# garden_control2.net
KiCad netlist of a schematic drawn in EAGLE
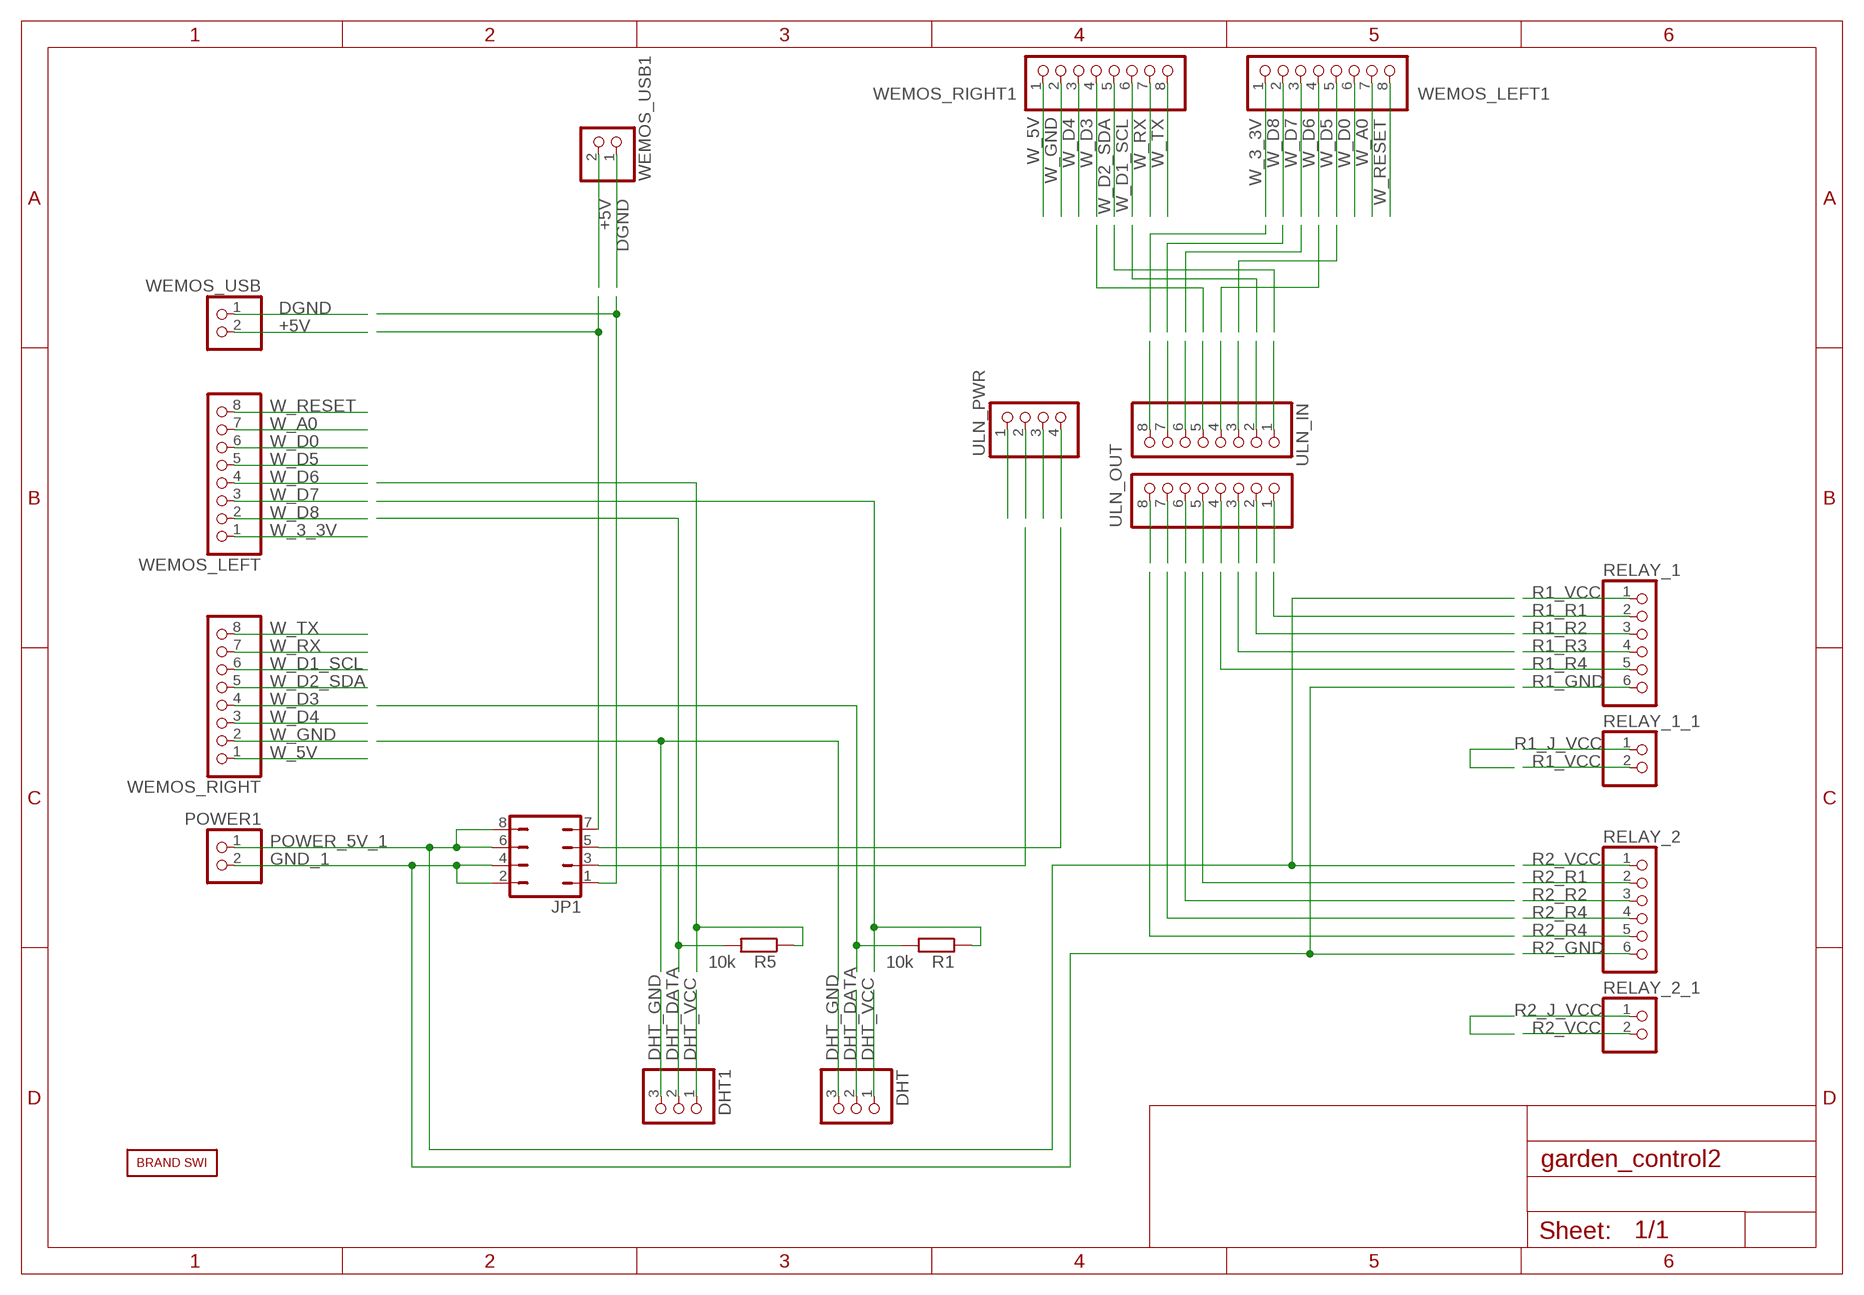
[diagram p0: schematic, sheet 1]

(export (version "E")
  (design (tool "Eeschema 10.0.6"))
  (components
    (comp (ref "DHT")
      (value "PINHD-1X3")
      (footprint "eagle-import:1X03")
      (libsource (lib "eagle-import") (part "PINHD-1X3"))
    )
    (comp (ref "DHT1")
      (value "PINHD-1X3")
      (footprint "eagle-import:1X03")
      (libsource (lib "eagle-import") (part "PINHD-1X3"))
    )
    (comp (ref "JP1")
      (value "JP4Q")
      (footprint "eagle-import:JP4Q")
      (libsource (lib "eagle-import") (part "JP4Q"))
    )
    (comp (ref "POWER1")
      (value "PINHD-1X2")
      (footprint "eagle-import:1X02")
      (libsource (lib "eagle-import") (part "PINHD-1X2"))
    )
    (comp (ref "R1")
      (value "10k")
      (footprint "eagle-import:0207_10")
      (libsource (lib "eagle-import") (part "R-EU_0207/10"))
    )
    (comp (ref "R5")
      (value "10k")
      (footprint "eagle-import:0207_10")
      (libsource (lib "eagle-import") (part "R-EU_0207/10"))
    )
    (comp (ref "RELAY_1")
      (value "PINHD-1X6")
      (footprint "eagle-import:1X06")
      (libsource (lib "eagle-import") (part "PINHD-1X6"))
    )
    (comp (ref "RELAY_1_1")
      (value "PINHD-1X2")
      (footprint "eagle-import:1X02")
      (libsource (lib "eagle-import") (part "PINHD-1X2"))
    )
    (comp (ref "RELAY_2")
      (value "PINHD-1X6")
      (footprint "eagle-import:1X06")
      (libsource (lib "eagle-import") (part "PINHD-1X6"))
    )
    (comp (ref "RELAY_2_1")
      (value "PINHD-1X2")
      (footprint "eagle-import:1X02")
      (libsource (lib "eagle-import") (part "PINHD-1X2"))
    )
    (comp (ref "U$2")
      (value "BRAND_SWI5X7")
      (footprint "eagle-import:BRAND_SWI_5X7")
      (libsource (lib "eagle-import") (part "BRAND_SWI5X7"))
    )
    (comp (ref "ULN_IN")
      (value "PINHD-1X8")
      (footprint "eagle-import:1X08")
      (libsource (lib "eagle-import") (part "PINHD-1X8"))
    )
    (comp (ref "ULN_OUT")
      (value "PINHD-1X8")
      (footprint "eagle-import:1X08")
      (libsource (lib "eagle-import") (part "PINHD-1X8"))
    )
    (comp (ref "ULN_PWR")
      (value "PINHD-1X4")
      (footprint "eagle-import:1X04")
      (libsource (lib "eagle-import") (part "PINHD-1X4"))
    )
    (comp (ref "WEMOS_LEFT")
      (value "PINHD-1X8")
      (footprint "eagle-import:1X08")
      (libsource (lib "eagle-import") (part "PINHD-1X8"))
    )
    (comp (ref "WEMOS_LEFT1")
      (value "PINHD-1X8")
      (footprint "eagle-import:1X08")
      (libsource (lib "eagle-import") (part "PINHD-1X8"))
    )
    (comp (ref "WEMOS_RIGHT")
      (value "PINHD-1X8")
      (footprint "eagle-import:1X08")
      (libsource (lib "eagle-import") (part "PINHD-1X8"))
    )
    (comp (ref "WEMOS_RIGHT1")
      (value "PINHD-1X8")
      (footprint "eagle-import:1X08")
      (libsource (lib "eagle-import") (part "PINHD-1X8"))
    )
    (comp (ref "WEMOS_USB")
      (value "PINHD-1X2")
      (footprint "eagle-import:1X02")
      (libsource (lib "eagle-import") (part "PINHD-1X2"))
    )
    (comp (ref "WEMOS_USB1")
      (value "PINHD-1X2")
      (footprint "eagle-import:1X02")
      (libsource (lib "eagle-import") (part "PINHD-1X2"))
    )
  )
  (nets
    (net (code "1") (name "/+5V") (class "Default")
      (node (ref "WEMOS_USB") (pin "2") (pinfunction "2_2") (pintype "passive"))
      (node (ref "WEMOS_USB1") (pin "2") (pinfunction "2_2") (pintype "passive"))
    )
    (net (code "2") (name "/DGND") (class "Default")
      (node (ref "WEMOS_USB") (pin "1") (pinfunction "1_1") (pintype "passive"))
      (node (ref "WEMOS_USB1") (pin "1") (pinfunction "1_1") (pintype "passive"))
    )
    (net (code "3") (name "/DHT_DATA") (class "Default")
      (node (ref "DHT") (pin "2") (pinfunction "2_2") (pintype "passive"))
      (node (ref "DHT1") (pin "2") (pinfunction "2_2") (pintype "passive"))
    )
    (net (code "4") (name "/DHT_GND") (class "Default")
      (node (ref "DHT") (pin "3") (pinfunction "3_3") (pintype "passive"))
      (node (ref "DHT1") (pin "3") (pinfunction "3_3") (pintype "passive"))
    )
    (net (code "5") (name "/DHT_VCC") (class "Default")
      (node (ref "DHT") (pin "1") (pinfunction "1_1") (pintype "passive"))
      (node (ref "DHT1") (pin "1") (pinfunction "1_1") (pintype "passive"))
    )
    (net (code "6") (name "/GND_1") (class "Default")
      (node (ref "JP1") (pin "2") (pinfunction "2_2") (pintype "passive"))
      (node (ref "JP1") (pin "4") (pinfunction "4_4") (pintype "passive"))
      (node (ref "POWER1") (pin "2") (pinfunction "2_2") (pintype "passive"))
    )
    (net (code "7") (name "/POWER_5V_1") (class "Default")
      (node (ref "JP1") (pin "6") (pinfunction "6_6") (pintype "passive"))
      (node (ref "JP1") (pin "8") (pinfunction "8_8") (pintype "passive"))
      (node (ref "POWER1") (pin "1") (pinfunction "1_1") (pintype "passive"))
    )
    (net (code "8") (name "/R1_GND") (class "Default")
      (node (ref "RELAY_1") (pin "6") (pinfunction "6_6") (pintype "passive"))
    )
    (net (code "9") (name "/R1_J_VCC") (class "Default")
      (node (ref "RELAY_1_1") (pin "1") (pinfunction "1_1") (pintype "passive"))
    )
    (net (code "10") (name "/R1_R1") (class "Default")
      (node (ref "RELAY_1") (pin "2") (pinfunction "2_2") (pintype "passive"))
    )
    (net (code "11") (name "/R1_R2") (class "Default")
      (node (ref "RELAY_1") (pin "3") (pinfunction "3_3") (pintype "passive"))
    )
    (net (code "12") (name "/R1_R3") (class "Default")
      (node (ref "RELAY_1") (pin "4") (pinfunction "4_4") (pintype "passive"))
    )
    (net (code "13") (name "/R1_R4") (class "Default")
      (node (ref "RELAY_1") (pin "5") (pinfunction "5_5") (pintype "passive"))
    )
    (net (code "14") (name "/R1_VCC") (class "Default")
      (node (ref "RELAY_1") (pin "1") (pinfunction "1_1") (pintype "passive"))
      (node (ref "RELAY_1_1") (pin "2") (pinfunction "2_2") (pintype "passive"))
    )
    (net (code "15") (name "/R2_GND") (class "Default")
      (node (ref "RELAY_2") (pin "6") (pinfunction "6_6") (pintype "passive"))
    )
    (net (code "16") (name "/R2_J_VCC") (class "Default")
      (node (ref "RELAY_2_1") (pin "1") (pinfunction "1_1") (pintype "passive"))
    )
    (net (code "17") (name "/R2_R1") (class "Default")
      (node (ref "RELAY_2") (pin "2") (pinfunction "2_2") (pintype "passive"))
    )
    (net (code "18") (name "/R2_R2") (class "Default")
      (node (ref "RELAY_2") (pin "3") (pinfunction "3_3") (pintype "passive"))
    )
    (net (code "19") (name "/R2_R4") (class "Default")
      (node (ref "RELAY_2") (pin "4") (pinfunction "4_4") (pintype "passive"))
      (node (ref "RELAY_2") (pin "5") (pinfunction "5_5") (pintype "passive"))
    )
    (net (code "20") (name "/R2_VCC") (class "Default")
      (node (ref "RELAY_2") (pin "1") (pinfunction "1_1") (pintype "passive"))
      (node (ref "RELAY_2_1") (pin "2") (pinfunction "2_2") (pintype "passive"))
    )
    (net (code "21") (name "/W_3_3V") (class "Default")
      (node (ref "WEMOS_LEFT") (pin "1") (pinfunction "1_1") (pintype "passive"))
      (node (ref "WEMOS_LEFT1") (pin "1") (pinfunction "1_1") (pintype "passive"))
    )
    (net (code "22") (name "/W_5V") (class "Default")
      (node (ref "WEMOS_RIGHT") (pin "1") (pinfunction "1_1") (pintype "passive"))
      (node (ref "WEMOS_RIGHT1") (pin "1") (pinfunction "1_1") (pintype "passive"))
    )
    (net (code "23") (name "/W_A0") (class "Default")
      (node (ref "WEMOS_LEFT") (pin "7") (pinfunction "7_7") (pintype "passive"))
      (node (ref "WEMOS_LEFT1") (pin "7") (pinfunction "7_7") (pintype "passive"))
    )
    (net (code "24") (name "/W_D0") (class "Default")
      (node (ref "WEMOS_LEFT") (pin "6") (pinfunction "6_6") (pintype "passive"))
      (node (ref "WEMOS_LEFT1") (pin "6") (pinfunction "6_6") (pintype "passive"))
    )
    (net (code "25") (name "/W_D1_SCL") (class "Default")
      (node (ref "WEMOS_RIGHT") (pin "6") (pinfunction "6_6") (pintype "passive"))
      (node (ref "WEMOS_RIGHT1") (pin "6") (pinfunction "6_6") (pintype "passive"))
    )
    (net (code "26") (name "/W_D2_SDA") (class "Default")
      (node (ref "WEMOS_RIGHT") (pin "5") (pinfunction "5_5") (pintype "passive"))
      (node (ref "WEMOS_RIGHT1") (pin "5") (pinfunction "5_5") (pintype "passive"))
    )
    (net (code "27") (name "/W_D3") (class "Default")
      (node (ref "WEMOS_RIGHT") (pin "4") (pinfunction "4_4") (pintype "passive"))
      (node (ref "WEMOS_RIGHT1") (pin "4") (pinfunction "4_4") (pintype "passive"))
    )
    (net (code "28") (name "/W_D4") (class "Default")
      (node (ref "WEMOS_RIGHT") (pin "3") (pinfunction "3_3") (pintype "passive"))
      (node (ref "WEMOS_RIGHT1") (pin "3") (pinfunction "3_3") (pintype "passive"))
    )
    (net (code "29") (name "/W_D5") (class "Default")
      (node (ref "WEMOS_LEFT") (pin "5") (pinfunction "5_5") (pintype "passive"))
      (node (ref "WEMOS_LEFT1") (pin "5") (pinfunction "5_5") (pintype "passive"))
    )
    (net (code "30") (name "/W_D6") (class "Default")
      (node (ref "WEMOS_LEFT") (pin "4") (pinfunction "4_4") (pintype "passive"))
      (node (ref "WEMOS_LEFT1") (pin "4") (pinfunction "4_4") (pintype "passive"))
    )
    (net (code "31") (name "/W_D7") (class "Default")
      (node (ref "WEMOS_LEFT") (pin "3") (pinfunction "3_3") (pintype "passive"))
      (node (ref "WEMOS_LEFT1") (pin "3") (pinfunction "3_3") (pintype "passive"))
    )
    (net (code "32") (name "/W_D8") (class "Default")
      (node (ref "WEMOS_LEFT") (pin "2") (pinfunction "2_2") (pintype "passive"))
      (node (ref "WEMOS_LEFT1") (pin "2") (pinfunction "2_2") (pintype "passive"))
    )
    (net (code "33") (name "/W_GND") (class "Default")
      (node (ref "WEMOS_RIGHT") (pin "2") (pinfunction "2_2") (pintype "passive"))
      (node (ref "WEMOS_RIGHT1") (pin "2") (pinfunction "2_2") (pintype "passive"))
    )
    (net (code "34") (name "/W_RESET") (class "Default")
      (node (ref "WEMOS_LEFT") (pin "8") (pinfunction "8_8") (pintype "passive"))
      (node (ref "WEMOS_LEFT1") (pin "8") (pinfunction "8_8") (pintype "passive"))
    )
    (net (code "35") (name "/W_RX") (class "Default")
      (node (ref "WEMOS_RIGHT") (pin "7") (pinfunction "7_7") (pintype "passive"))
      (node (ref "WEMOS_RIGHT1") (pin "7") (pinfunction "7_7") (pintype "passive"))
    )
    (net (code "36") (name "/W_TX") (class "Default")
      (node (ref "WEMOS_RIGHT") (pin "8") (pinfunction "8_8") (pintype "passive"))
      (node (ref "WEMOS_RIGHT1") (pin "8") (pinfunction "8_8") (pintype "passive"))
    )
    (net (code "37") (name "unconnected-(JP1-Pad1)") (class "Default")
      (node (ref "JP1") (pin "1") (pinfunction "1_1") (pintype "passive"))
    )
    (net (code "38") (name "unconnected-(JP1-Pad3)") (class "Default")
      (node (ref "JP1") (pin "3") (pinfunction "3_3") (pintype "passive"))
    )
    (net (code "39") (name "unconnected-(JP1-Pad5)") (class "Default")
      (node (ref "JP1") (pin "5") (pinfunction "5_5") (pintype "passive"))
    )
    (net (code "40") (name "unconnected-(JP1-Pad7)") (class "Default")
      (node (ref "JP1") (pin "7") (pinfunction "7_7") (pintype "passive"))
    )
    (net (code "41") (name "unconnected-(R1-Pad1)") (class "Default")
      (node (ref "R1") (pin "1") (pinfunction "1_1") (pintype "passive"))
    )
    (net (code "42") (name "unconnected-(R1-Pad2)") (class "Default")
      (node (ref "R1") (pin "2") (pinfunction "2_2") (pintype "passive"))
    )
    (net (code "43") (name "unconnected-(R5-Pad1)") (class "Default")
      (node (ref "R5") (pin "1") (pinfunction "1_1") (pintype "passive"))
    )
    (net (code "44") (name "unconnected-(R5-Pad2)") (class "Default")
      (node (ref "R5") (pin "2") (pinfunction "2_2") (pintype "passive"))
    )
    (net (code "45") (name "unconnected-(ULN_IN-Pad1)") (class "Default")
      (node (ref "ULN_IN") (pin "1") (pinfunction "1_1") (pintype "passive"))
    )
    (net (code "46") (name "unconnected-(ULN_IN-Pad2)") (class "Default")
      (node (ref "ULN_IN") (pin "2") (pinfunction "2_2") (pintype "passive"))
    )
    (net (code "47") (name "unconnected-(ULN_IN-Pad3)") (class "Default")
      (node (ref "ULN_IN") (pin "3") (pinfunction "3_3") (pintype "passive"))
    )
    (net (code "48") (name "unconnected-(ULN_IN-Pad4)") (class "Default")
      (node (ref "ULN_IN") (pin "4") (pinfunction "4_4") (pintype "passive"))
    )
    (net (code "49") (name "unconnected-(ULN_IN-Pad5)") (class "Default")
      (node (ref "ULN_IN") (pin "5") (pinfunction "5_5") (pintype "passive"))
    )
    (net (code "50") (name "unconnected-(ULN_IN-Pad6)") (class "Default")
      (node (ref "ULN_IN") (pin "6") (pinfunction "6_6") (pintype "passive"))
    )
    (net (code "51") (name "unconnected-(ULN_IN-Pad7)") (class "Default")
      (node (ref "ULN_IN") (pin "7") (pinfunction "7_7") (pintype "passive"))
    )
    (net (code "52") (name "unconnected-(ULN_IN-Pad8)") (class "Default")
      (node (ref "ULN_IN") (pin "8") (pinfunction "8_8") (pintype "passive"))
    )
    (net (code "53") (name "unconnected-(ULN_OUT-Pad1)") (class "Default")
      (node (ref "ULN_OUT") (pin "1") (pinfunction "1_1") (pintype "passive"))
    )
    (net (code "54") (name "unconnected-(ULN_OUT-Pad2)") (class "Default")
      (node (ref "ULN_OUT") (pin "2") (pinfunction "2_2") (pintype "passive"))
    )
    (net (code "55") (name "unconnected-(ULN_OUT-Pad3)") (class "Default")
      (node (ref "ULN_OUT") (pin "3") (pinfunction "3_3") (pintype "passive"))
    )
    (net (code "56") (name "unconnected-(ULN_OUT-Pad4)") (class "Default")
      (node (ref "ULN_OUT") (pin "4") (pinfunction "4_4") (pintype "passive"))
    )
    (net (code "57") (name "unconnected-(ULN_OUT-Pad5)") (class "Default")
      (node (ref "ULN_OUT") (pin "5") (pinfunction "5_5") (pintype "passive"))
    )
    (net (code "58") (name "unconnected-(ULN_OUT-Pad6)") (class "Default")
      (node (ref "ULN_OUT") (pin "6") (pinfunction "6_6") (pintype "passive"))
    )
    (net (code "59") (name "unconnected-(ULN_OUT-Pad7)") (class "Default")
      (node (ref "ULN_OUT") (pin "7") (pinfunction "7_7") (pintype "passive"))
    )
    (net (code "60") (name "unconnected-(ULN_OUT-Pad8)") (class "Default")
      (node (ref "ULN_OUT") (pin "8") (pinfunction "8_8") (pintype "passive"))
    )
    (net (code "61") (name "unconnected-(ULN_PWR-Pad1)") (class "Default")
      (node (ref "ULN_PWR") (pin "1") (pinfunction "1_1") (pintype "passive"))
    )
    (net (code "62") (name "unconnected-(ULN_PWR-Pad2)") (class "Default")
      (node (ref "ULN_PWR") (pin "2") (pinfunction "2_2") (pintype "passive"))
    )
    (net (code "63") (name "unconnected-(ULN_PWR-Pad3)") (class "Default")
      (node (ref "ULN_PWR") (pin "3") (pinfunction "3_3") (pintype "passive"))
    )
    (net (code "64") (name "unconnected-(ULN_PWR-Pad4)") (class "Default")
      (node (ref "ULN_PWR") (pin "4") (pinfunction "4_4") (pintype "passive"))
    )
  )
)
